# SolarPanels.net
KiCad netlist of a schematic drawn in Altium Designer
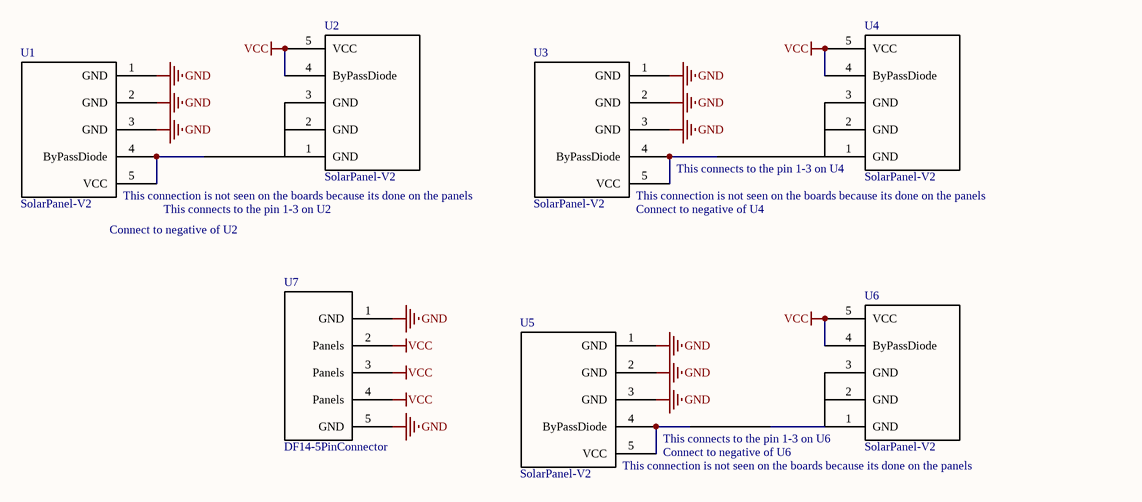
[diagram p0: SolarPanels.SchDoc]

(export (version "E")
  (design (tool "Eeschema 10.0.6"))
  (components
    (comp (ref "U1")
      (value "SolarPanel-V2")
      (footprint "SolarPanel_V2_1")
      (libsource (lib "SolarPanelsSchematicLibrary") (part "SolarPanel-V2"))
    )
    (comp (ref "U2")
      (value "SolarPanel-V2")
      (footprint "SOLARPANEL_V2_2")
      (libsource (lib "SolarPanelsSchematicLibrary") (part "SolarPanel-V2"))
    )
    (comp (ref "U3")
      (value "SolarPanel-V2")
      (footprint "SolarPanel_V2_1")
      (libsource (lib "SolarPanelsSchematicLibrary") (part "SolarPanel-V2"))
    )
    (comp (ref "U4")
      (value "SolarPanel-V2")
      (footprint "SOLARPANEL_V2_2")
      (libsource (lib "SolarPanelsSchematicLibrary") (part "SolarPanel-V2"))
    )
    (comp (ref "U5")
      (value "SolarPanel-V2")
      (footprint "SolarPanel_V2_1")
      (libsource (lib "SolarPanelsSchematicLibrary") (part "SolarPanel-V2"))
    )
    (comp (ref "U6")
      (value "SolarPanel-V2")
      (footprint "SOLARPANEL_V2_2")
      (libsource (lib "SolarPanelsSchematicLibrary") (part "SolarPanel-V2"))
    )
    (comp (ref "U7")
      (value "DF14-5PinConnector")
      (footprint "DF14-5P-1.25H(55)")
      (libsource (lib "SolarPanelsSchematicLibrary") (part "DF14-5PinConnector"))
    )
  )
  (nets
    (net (code "1") (name "GND") (class "Default")
      (node (ref "U1") (pin "1") (pinfunction "GND_1") (pintype "power_in"))
      (node (ref "U1") (pin "2") (pinfunction "GND_2") (pintype "passive"))
      (node (ref "U1") (pin "3") (pinfunction "GND_3") (pintype "power_in"))
      (node (ref "U3") (pin "1") (pinfunction "GND_1") (pintype "power_in"))
      (node (ref "U3") (pin "2") (pinfunction "GND_2") (pintype "passive"))
      (node (ref "U3") (pin "3") (pinfunction "GND_3") (pintype "power_in"))
      (node (ref "U5") (pin "1") (pinfunction "GND_1") (pintype "power_in"))
      (node (ref "U5") (pin "2") (pinfunction "GND_2") (pintype "passive"))
      (node (ref "U5") (pin "3") (pinfunction "GND_3") (pintype "power_in"))
      (node (ref "U7") (pin "1") (pinfunction "GND_1") (pintype "passive"))
      (node (ref "U7") (pin "5") (pinfunction "GND_5") (pintype "passive"))
    )
    (net (code "2") (name "Net-(U1-ByPassDiode)") (class "Default")
      (node (ref "U1") (pin "4") (pinfunction "ByPassDiode_4") (pintype "power_in"))
      (node (ref "U1") (pin "5") (pinfunction "VCC_5") (pintype "passive"))
    )
    (net (code "3") (name "Net-(U3-ByPassDiode)") (class "Default")
      (node (ref "U3") (pin "4") (pinfunction "ByPassDiode_4") (pintype "power_in"))
      (node (ref "U3") (pin "5") (pinfunction "VCC_5") (pintype "passive"))
    )
    (net (code "4") (name "Net-(U5-ByPassDiode)") (class "Default")
      (node (ref "U5") (pin "4") (pinfunction "ByPassDiode_4") (pintype "power_in"))
      (node (ref "U5") (pin "5") (pinfunction "VCC_5") (pintype "passive"))
    )
    (net (code "5") (name "VCC") (class "Default")
      (node (ref "U2") (pin "4") (pinfunction "ByPassDiode_4") (pintype "power_in"))
      (node (ref "U2") (pin "5") (pinfunction "VCC_5") (pintype "passive"))
      (node (ref "U4") (pin "4") (pinfunction "ByPassDiode_4") (pintype "power_in"))
      (node (ref "U4") (pin "5") (pinfunction "VCC_5") (pintype "passive"))
      (node (ref "U6") (pin "4") (pinfunction "ByPassDiode_4") (pintype "power_in"))
      (node (ref "U6") (pin "5") (pinfunction "VCC_5") (pintype "passive"))
      (node (ref "U7") (pin "2") (pinfunction "Panels_2") (pintype "passive"))
      (node (ref "U7") (pin "3") (pinfunction "Panels_3") (pintype "passive"))
      (node (ref "U7") (pin "4") (pinfunction "Panels_4") (pintype "passive"))
    )
    (net (code "6") (name "unconnected-(U2-GND-Pad1)") (class "Default")
      (node (ref "U2") (pin "1") (pinfunction "GND_1") (pintype "power_in"))
    )
    (net (code "7") (name "unconnected-(U2-GND-Pad2)") (class "Default")
      (node (ref "U2") (pin "2") (pinfunction "GND_2") (pintype "passive"))
    )
    (net (code "8") (name "unconnected-(U2-GND-Pad3)") (class "Default")
      (node (ref "U2") (pin "3") (pinfunction "GND_3") (pintype "power_in"))
    )
    (net (code "9") (name "unconnected-(U4-GND-Pad1)") (class "Default")
      (node (ref "U4") (pin "1") (pinfunction "GND_1") (pintype "power_in"))
    )
    (net (code "10") (name "unconnected-(U4-GND-Pad2)") (class "Default")
      (node (ref "U4") (pin "2") (pinfunction "GND_2") (pintype "passive"))
    )
    (net (code "11") (name "unconnected-(U4-GND-Pad3)") (class "Default")
      (node (ref "U4") (pin "3") (pinfunction "GND_3") (pintype "power_in"))
    )
    (net (code "12") (name "unconnected-(U6-GND-Pad1)") (class "Default")
      (node (ref "U6") (pin "1") (pinfunction "GND_1") (pintype "power_in"))
    )
    (net (code "13") (name "unconnected-(U6-GND-Pad2)") (class "Default")
      (node (ref "U6") (pin "2") (pinfunction "GND_2") (pintype "passive"))
    )
    (net (code "14") (name "unconnected-(U6-GND-Pad3)") (class "Default")
      (node (ref "U6") (pin "3") (pinfunction "GND_3") (pintype "power_in"))
    )
  )
)
